# RNS_board.net
KiCad netlist of a schematic drawn in EAGLE
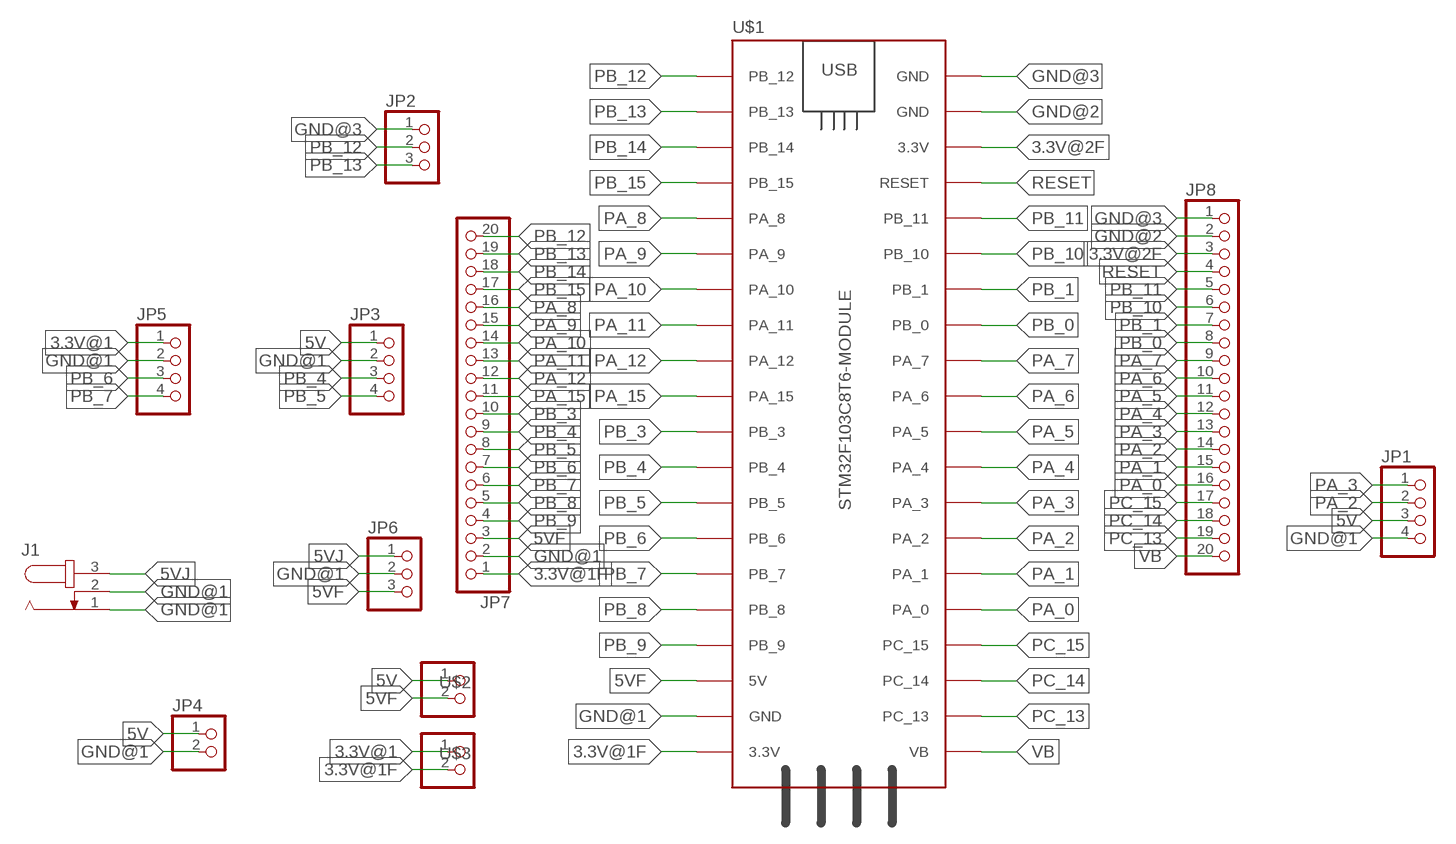
[diagram p0: schematic, sheet 1]

(export (version "E")
  (design (tool "Eeschema 10.0.6"))
  (components
    (comp (ref "J1")
      (value "JACK-PLUG0")
      (footprint "eagle-import:SPC4077")
      (libsource (lib "eagle-import") (part "JACK-PLUG0"))
    )
    (comp (ref "JP1")
      (value "PINHD-1X4")
      (footprint "eagle-import:1X04")
      (libsource (lib "eagle-import") (part "MIA_LIBRARY-2-2-2_PINHD-1X4"))
    )
    (comp (ref "JP2")
      (value "PINHD-1X3")
      (footprint "eagle-import:1X03")
      (libsource (lib "eagle-import") (part "PINHD-1X3"))
    )
    (comp (ref "JP3")
      (value "PINHD-1X4")
      (footprint "eagle-import:1X04")
      (libsource (lib "eagle-import") (part "MIA_LIBRARY-2-2-2_PINHD-1X4"))
    )
    (comp (ref "JP4")
      (value "PINHD-1X2")
      (footprint "eagle-import:1X02")
      (libsource (lib "eagle-import") (part "PINHD-1X2"))
    )
    (comp (ref "JP5")
      (value "PINHD-1X4")
      (footprint "eagle-import:1X04")
      (libsource (lib "eagle-import") (part "PINHD-1X4"))
    )
    (comp (ref "JP6")
      (value "PINHD-1X3")
      (footprint "eagle-import:1X03")
      (libsource (lib "eagle-import") (part "MIA_LIBRARY-2-2-2_PINHD-1X3"))
    )
    (comp (ref "JP7")
      (value "PINHD-1X20")
      (footprint "eagle-import:1X20")
      (libsource (lib "eagle-import") (part "PINHD-1X20"))
    )
    (comp (ref "JP8")
      (value "PINHD-1X20")
      (footprint "eagle-import:1X20")
      (libsource (lib "eagle-import") (part "PINHD-1X20"))
    )
    (comp (ref "U$1")
      (value "STM32F103C8T6-MODULE")
      (footprint "eagle-import:STM32F103C8T6-MODULE")
      (libsource (lib "eagle-import") (part "STM32F103C8T6-MODULE"))
    )
    (comp (ref "U$2")
      (value "PINHD-1X2")
      (footprint "eagle-import:1X02")
      (libsource (lib "eagle-import") (part "PINHD-1X2"))
    )
    (comp (ref "U$3")
      (value "PINHD-1X2")
      (footprint "eagle-import:1X02")
      (libsource (lib "eagle-import") (part "PINHD-1X2"))
    )
  )
  (nets
    (net (code "1") (name "3.3V@1") (class "Default")
      (node (ref "JP5") (pin "1") (pinfunction "1_1") (pintype "passive"))
      (node (ref "U$3") (pin "1") (pinfunction "1_1") (pintype "passive"))
    )
    (net (code "2") (name "3.3V@1F") (class "Default")
      (node (ref "JP7") (pin "1") (pinfunction "1_1") (pintype "passive"))
      (node (ref "U$1") (pin "3.3V_1") (pinfunction "3.3V_3.3V_1") (pintype "bidirectional"))
      (node (ref "U$3") (pin "2") (pinfunction "2_2") (pintype "passive"))
    )
    (net (code "3") (name "3.3V@2F") (class "Default")
      (node (ref "JP8") (pin "3") (pinfunction "3_3") (pintype "passive"))
      (node (ref "U$1") (pin "3.3V_2") (pinfunction "3.3V_3.3V_2") (pintype "bidirectional"))
    )
    (net (code "4") (name "5V") (class "Default")
      (node (ref "JP1") (pin "3") (pinfunction "3_3") (pintype "passive"))
      (node (ref "JP3") (pin "1") (pinfunction "1_1") (pintype "passive"))
      (node (ref "JP4") (pin "1") (pinfunction "1_1") (pintype "passive"))
      (node (ref "U$2") (pin "1") (pinfunction "1_1") (pintype "passive"))
    )
    (net (code "5") (name "5VF") (class "Default")
      (node (ref "JP6") (pin "3") (pinfunction "3_3") (pintype "passive"))
      (node (ref "JP7") (pin "3") (pinfunction "3_3") (pintype "passive"))
      (node (ref "U$1") (pin "5V") (pinfunction "5V_5V") (pintype "bidirectional"))
      (node (ref "U$2") (pin "2") (pinfunction "2_2") (pintype "passive"))
    )
    (net (code "6") (name "5VJ") (class "Default")
      (node (ref "J1") (pin "3") (pinfunction "3_3") (pintype "passive"))
      (node (ref "JP6") (pin "1") (pinfunction "1_1") (pintype "passive"))
    )
    (net (code "7") (name "GND@1") (class "Default")
      (node (ref "J1") (pin "1") (pinfunction "1_1") (pintype "passive"))
      (node (ref "J1") (pin "2") (pinfunction "2_2") (pintype "passive"))
      (node (ref "JP1") (pin "4") (pinfunction "4_4") (pintype "passive"))
      (node (ref "JP3") (pin "2") (pinfunction "2_2") (pintype "passive"))
      (node (ref "JP4") (pin "2") (pinfunction "2_2") (pintype "passive"))
      (node (ref "JP5") (pin "2") (pinfunction "2_2") (pintype "passive"))
      (node (ref "JP6") (pin "2") (pinfunction "2_2") (pintype "passive"))
      (node (ref "JP7") (pin "2") (pinfunction "2_2") (pintype "passive"))
      (node (ref "U$1") (pin "GND_1") (pinfunction "GND_GND_1") (pintype "bidirectional"))
    )
    (net (code "8") (name "GND@2") (class "Default")
      (node (ref "JP8") (pin "2") (pinfunction "2_2") (pintype "passive"))
      (node (ref "U$1") (pin "GND_2") (pinfunction "GND_GND_2") (pintype "bidirectional"))
    )
    (net (code "9") (name "GND@3") (class "Default")
      (node (ref "JP2") (pin "1") (pinfunction "1_1") (pintype "passive"))
      (node (ref "JP8") (pin "1") (pinfunction "1_1") (pintype "passive"))
      (node (ref "U$1") (pin "GND_3") (pinfunction "GND_GND_3") (pintype "power_in"))
    )
    (net (code "10") (name "PA_0") (class "Default")
      (node (ref "JP8") (pin "16") (pinfunction "16_16") (pintype "passive"))
      (node (ref "U$1") (pin "PA_0") (pinfunction "PA_0_PA_0") (pintype "bidirectional"))
    )
    (net (code "11") (name "PA_1") (class "Default")
      (node (ref "JP8") (pin "15") (pinfunction "15_15") (pintype "passive"))
      (node (ref "U$1") (pin "PA_1") (pinfunction "PA_1_PA_1") (pintype "bidirectional"))
    )
    (net (code "12") (name "PA_2") (class "Default")
      (node (ref "JP1") (pin "2") (pinfunction "2_2") (pintype "passive"))
      (node (ref "JP8") (pin "14") (pinfunction "14_14") (pintype "passive"))
      (node (ref "U$1") (pin "PA_2") (pinfunction "PA_2_PA_2") (pintype "bidirectional"))
    )
    (net (code "13") (name "PA_3") (class "Default")
      (node (ref "JP1") (pin "1") (pinfunction "1_1") (pintype "passive"))
      (node (ref "JP8") (pin "13") (pinfunction "13_13") (pintype "passive"))
      (node (ref "U$1") (pin "PA_3") (pinfunction "PA_3_PA_3") (pintype "bidirectional"))
    )
    (net (code "14") (name "PA_4") (class "Default")
      (node (ref "JP8") (pin "12") (pinfunction "12_12") (pintype "passive"))
      (node (ref "U$1") (pin "PA_4") (pinfunction "PA_4_PA_4") (pintype "bidirectional"))
    )
    (net (code "15") (name "PA_5") (class "Default")
      (node (ref "JP8") (pin "11") (pinfunction "11_11") (pintype "passive"))
      (node (ref "U$1") (pin "PA_5") (pinfunction "PA_5_PA_5") (pintype "bidirectional"))
    )
    (net (code "16") (name "PA_6") (class "Default")
      (node (ref "JP8") (pin "10") (pinfunction "10_10") (pintype "passive"))
      (node (ref "U$1") (pin "PA_6") (pinfunction "PA_6_PA_6") (pintype "bidirectional"))
    )
    (net (code "17") (name "PA_7") (class "Default")
      (node (ref "JP8") (pin "9") (pinfunction "9_9") (pintype "passive"))
      (node (ref "U$1") (pin "PA_7") (pinfunction "PA_7_PA_7") (pintype "bidirectional"))
    )
    (net (code "18") (name "PA_8") (class "Default")
      (node (ref "JP7") (pin "16") (pinfunction "16_16") (pintype "passive"))
      (node (ref "U$1") (pin "PA_8") (pinfunction "PA_8_PA_8") (pintype "bidirectional"))
    )
    (net (code "19") (name "PA_9") (class "Default")
      (node (ref "JP7") (pin "15") (pinfunction "15_15") (pintype "passive"))
      (node (ref "U$1") (pin "PA_9") (pinfunction "PA_9_PA_9") (pintype "bidirectional"))
    )
    (net (code "20") (name "PA_10") (class "Default")
      (node (ref "JP7") (pin "14") (pinfunction "14_14") (pintype "passive"))
      (node (ref "U$1") (pin "PA_10") (pinfunction "PA_10_PA_10") (pintype "bidirectional"))
    )
    (net (code "21") (name "PA_11") (class "Default")
      (node (ref "JP7") (pin "13") (pinfunction "13_13") (pintype "passive"))
      (node (ref "U$1") (pin "PA_11") (pinfunction "PA_11_PA_11") (pintype "bidirectional"))
    )
    (net (code "22") (name "PA_12") (class "Default")
      (node (ref "JP7") (pin "12") (pinfunction "12_12") (pintype "passive"))
      (node (ref "U$1") (pin "PA_12") (pinfunction "PA_12_PA_12") (pintype "bidirectional"))
    )
    (net (code "23") (name "PA_15") (class "Default")
      (node (ref "JP7") (pin "11") (pinfunction "11_11") (pintype "passive"))
      (node (ref "U$1") (pin "PA_15") (pinfunction "PA_15_PA_15") (pintype "bidirectional"))
    )
    (net (code "24") (name "PB_0") (class "Default")
      (node (ref "JP8") (pin "8") (pinfunction "8_8") (pintype "passive"))
      (node (ref "U$1") (pin "PB_0") (pinfunction "PB_0_PB_0") (pintype "bidirectional"))
    )
    (net (code "25") (name "PB_1") (class "Default")
      (node (ref "JP8") (pin "7") (pinfunction "7_7") (pintype "passive"))
      (node (ref "U$1") (pin "PB_1") (pinfunction "PB_1_PB_1") (pintype "bidirectional"))
    )
    (net (code "26") (name "PB_3") (class "Default")
      (node (ref "JP7") (pin "10") (pinfunction "10_10") (pintype "passive"))
      (node (ref "U$1") (pin "PB_3") (pinfunction "PB_3_PB_3") (pintype "bidirectional"))
    )
    (net (code "27") (name "PB_4") (class "Default")
      (node (ref "JP3") (pin "3") (pinfunction "3_3") (pintype "passive"))
      (node (ref "JP7") (pin "9") (pinfunction "9_9") (pintype "passive"))
      (node (ref "U$1") (pin "PB_4") (pinfunction "PB_4_PB_4") (pintype "bidirectional"))
    )
    (net (code "28") (name "PB_5") (class "Default")
      (node (ref "JP3") (pin "4") (pinfunction "4_4") (pintype "passive"))
      (node (ref "JP7") (pin "8") (pinfunction "8_8") (pintype "passive"))
      (node (ref "U$1") (pin "PB_5") (pinfunction "PB_5_PB_5") (pintype "bidirectional"))
    )
    (net (code "29") (name "PB_6") (class "Default")
      (node (ref "JP5") (pin "3") (pinfunction "3_3") (pintype "passive"))
      (node (ref "JP7") (pin "7") (pinfunction "7_7") (pintype "passive"))
      (node (ref "U$1") (pin "PB_6") (pinfunction "PB_6_PB_6") (pintype "bidirectional"))
    )
    (net (code "30") (name "PB_7") (class "Default")
      (node (ref "JP5") (pin "4") (pinfunction "4_4") (pintype "passive"))
      (node (ref "JP7") (pin "6") (pinfunction "6_6") (pintype "passive"))
      (node (ref "U$1") (pin "PB_7") (pinfunction "PB_7_PB_7") (pintype "bidirectional"))
    )
    (net (code "31") (name "PB_8") (class "Default")
      (node (ref "JP7") (pin "5") (pinfunction "5_5") (pintype "passive"))
      (node (ref "U$1") (pin "PB_8") (pinfunction "PB_8_PB_8") (pintype "bidirectional"))
    )
    (net (code "32") (name "PB_9") (class "Default")
      (node (ref "JP7") (pin "4") (pinfunction "4_4") (pintype "passive"))
      (node (ref "U$1") (pin "PB_9") (pinfunction "PB_9_PB_9") (pintype "bidirectional"))
    )
    (net (code "33") (name "PB_10") (class "Default")
      (node (ref "JP8") (pin "6") (pinfunction "6_6") (pintype "passive"))
      (node (ref "U$1") (pin "PB_10") (pinfunction "PB_10_PB_10") (pintype "bidirectional"))
    )
    (net (code "34") (name "PB_11") (class "Default")
      (node (ref "JP8") (pin "5") (pinfunction "5_5") (pintype "passive"))
      (node (ref "U$1") (pin "PB_11") (pinfunction "PB_11_PB_11") (pintype "bidirectional"))
    )
    (net (code "35") (name "PB_12") (class "Default")
      (node (ref "JP2") (pin "2") (pinfunction "2_2") (pintype "passive"))
      (node (ref "JP7") (pin "20") (pinfunction "20_20") (pintype "passive"))
      (node (ref "U$1") (pin "PB_12") (pinfunction "PB_12_PB_12") (pintype "bidirectional"))
    )
    (net (code "36") (name "PB_13") (class "Default")
      (node (ref "JP2") (pin "3") (pinfunction "3_3") (pintype "passive"))
      (node (ref "JP7") (pin "19") (pinfunction "19_19") (pintype "passive"))
      (node (ref "U$1") (pin "PB_13") (pinfunction "PB_13_PB_13") (pintype "bidirectional"))
    )
    (net (code "37") (name "PB_14") (class "Default")
      (node (ref "JP7") (pin "18") (pinfunction "18_18") (pintype "passive"))
      (node (ref "U$1") (pin "PB_14") (pinfunction "PB_14_PB_14") (pintype "bidirectional"))
    )
    (net (code "38") (name "PB_15") (class "Default")
      (node (ref "JP7") (pin "17") (pinfunction "17_17") (pintype "passive"))
      (node (ref "U$1") (pin "PB_15") (pinfunction "PB_15_PB_15") (pintype "bidirectional"))
    )
    (net (code "39") (name "PC_13") (class "Default")
      (node (ref "JP8") (pin "19") (pinfunction "19_19") (pintype "passive"))
      (node (ref "U$1") (pin "PC_13") (pinfunction "PC_13_PC_13") (pintype "bidirectional"))
    )
    (net (code "40") (name "PC_14") (class "Default")
      (node (ref "JP8") (pin "18") (pinfunction "18_18") (pintype "passive"))
      (node (ref "U$1") (pin "PC_14") (pinfunction "PC_14_PC_14") (pintype "bidirectional"))
    )
    (net (code "41") (name "PC_15") (class "Default")
      (node (ref "JP8") (pin "17") (pinfunction "17_17") (pintype "passive"))
      (node (ref "U$1") (pin "PC_15") (pinfunction "PC_15_PC_15") (pintype "bidirectional"))
    )
    (net (code "42") (name "RESET") (class "Default")
      (node (ref "JP8") (pin "4") (pinfunction "4_4") (pintype "passive"))
      (node (ref "U$1") (pin "RESET") (pinfunction "RESET_RESET") (pintype "bidirectional"))
    )
    (net (code "43") (name "VB") (class "Default")
      (node (ref "JP8") (pin "20") (pinfunction "20_20") (pintype "passive"))
      (node (ref "U$1") (pin "VB") (pinfunction "VB_VB") (pintype "bidirectional"))
    )
  )
)
